# Sheet1_26Pin.net
KiCad netlist of a schematic drawn in Altium Designer
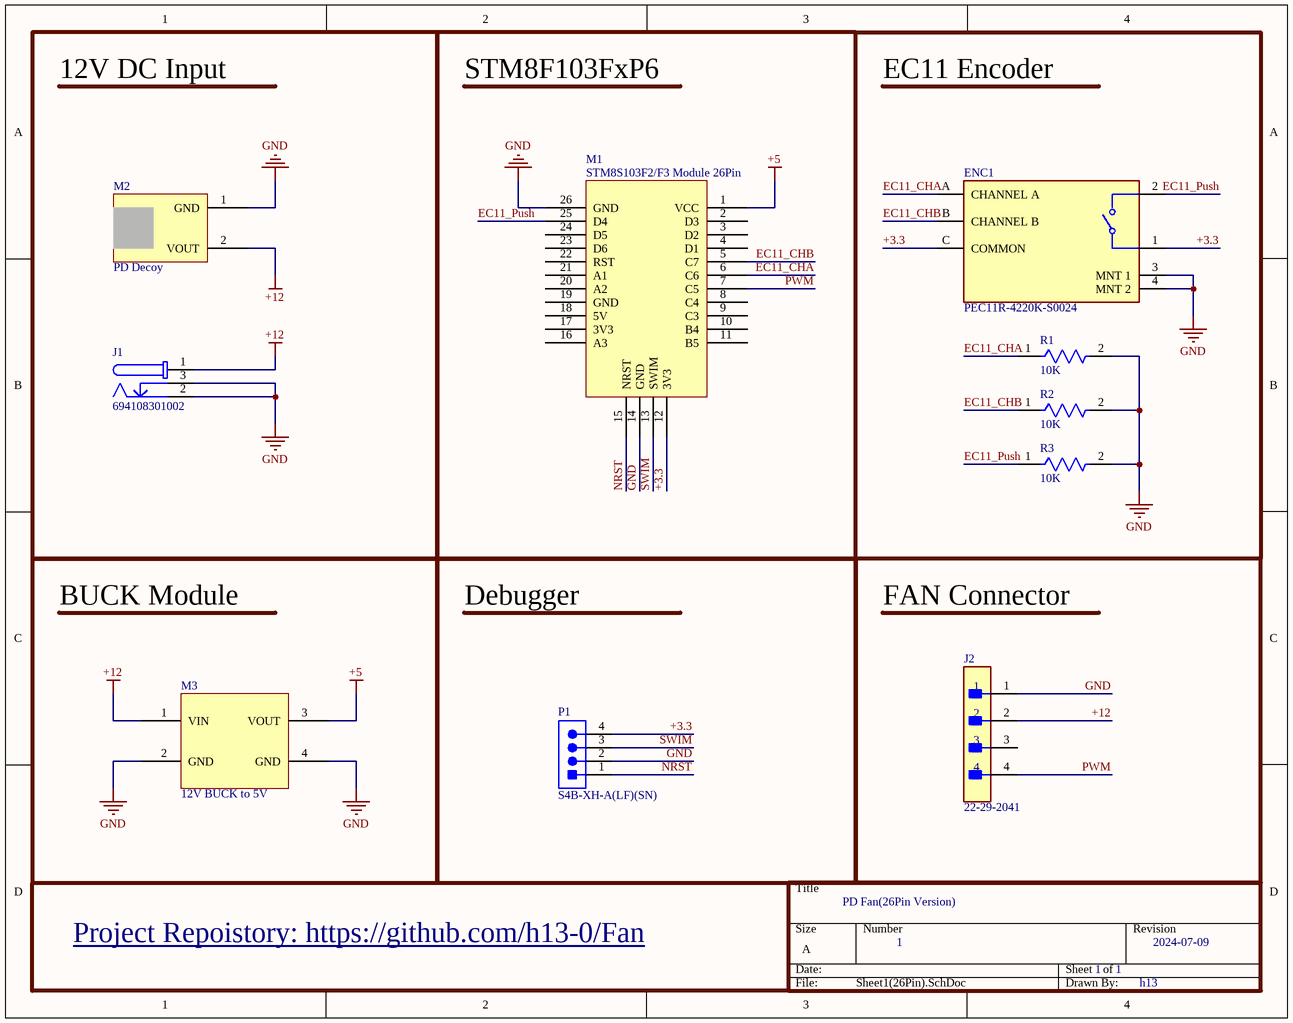
[diagram p0: Sheet1(26Pin).SchDoc]

(export (version "E")
  (design (tool "Eeschema 10.0.6"))
  (components
    (comp (ref "ENC1")
      (value "PEC11R-4220K-S0024")
      (footprint "EC11")
      (description "ROTARY ENCODER INCREMENTAL 24PPR")
      (libsource (lib "Altium Content Vault") (part "d75f9e24c474ed3fe2cf82f27e06f2a"))
    )
    (comp (ref "J1")
      (value "694108301002")
      (footprint "694108301002")
      (libsource (lib "Altium Content Vault") (part "DC Power Jack"))
    )
    (comp (ref "J2")
      (value "22-29-2041")
      (footprint "FP-22-29-2041-MFG")
      (description "CONN HEADER VERT 4POS 2.54MM")
      (libsource (lib "Altium Content Vault") (part "299a8cea1bdcbc3624fe62c390fa72c"))
    )
    (comp (ref "M1")
      (value "STM8S103F2/F3 Module 26Pin")
      (footprint "STM8FxP6 Module 26Pin")
      (libsource (lib "STM8S103F") (part "STM8S103F2/F3 Module"))
    )
    (comp (ref "M2") (value "PD Decoy") (footprint "PD Decoy") (libsource (lib "PD_Decoy") (part "PD Decoy")))
    (comp (ref "M3")
      (value "12V BUCK to 5V")
      (footprint "Buck Mini")
      (libsource (lib "BUCK_BOOST") (part "BUCK ¦ BOOST"))
    )
    (comp (ref "P1")
      (value "S4B-XH-A(LF)(SN)")
      (footprint "JST-S4B-XH-A(LF)(SN)_V")
      (libsource (lib "Altium Content Vault") (part "CN-1P-M-R4"))
    )
    (comp (ref "R1")
      (value "10K")
      (footprint "FP-MRS25-MFG")
      (description "RES 1K OHM 0.6W 1% AXIAL")
      (fields (field (name "TOLERANCE") "1%"))
      (libsource (lib "Altium Content Vault") (part "1029c3af85768c4190bb7ad29bc67b5"))
    )
    (comp (ref "R2")
      (value "10K")
      (footprint "FP-MRS25-MFG")
      (description "RES 1K OHM 0.6W 1% AXIAL")
      (fields (field (name "TOLERANCE") "1%"))
      (libsource (lib "Altium Content Vault") (part "1029c3af85768c4190bb7ad29bc67b5"))
    )
    (comp (ref "R3")
      (value "10K")
      (footprint "FP-MRS25-MFG")
      (description "RES 1K OHM 0.6W 1% AXIAL")
      (fields (field (name "TOLERANCE") "1%"))
      (libsource (lib "Altium Content Vault") (part "1029c3af85768c4190bb7ad29bc67b5"))
    )
  )
  (nets
    (net (code "1") (name "+5") (class "Default")
      (node (ref "M1") (pin "1") (pinfunction "VCC_1") (pintype "passive"))
      (node (ref "M3") (pin "3") (pinfunction "VOUT_3") (pintype "passive"))
    )
    (net (code "2") (name "+12") (class "Default")
      (node (ref "J1") (pin "1") (pinfunction "1_1") (pintype "passive"))
      (node (ref "J2") (pin "2") (pinfunction "2_2") (pintype "passive"))
      (node (ref "M2") (pin "2") (pinfunction "VOUT_2") (pintype "passive"))
      (node (ref "M3") (pin "1") (pinfunction "VIN_1") (pintype "passive"))
    )
    (net (code "3") (name "/+3.3") (class "Default")
      (node (ref "ENC1") (pin "1") (pinfunction "1_1") (pintype "passive"))
      (node (ref "ENC1") (pin "C") (pinfunction "COMMON_C") (pintype "passive"))
      (node (ref "M1") (pin "12") (pinfunction "3V3_12") (pintype "passive"))
      (node (ref "P1") (pin "4") (pinfunction "4_4") (pintype "passive"))
    )
    (net (code "4") (name "/EC11_CHA") (class "Default")
      (node (ref "ENC1") (pin "A") (pinfunction "CHANNEL_A_A") (pintype "passive"))
      (node (ref "M1") (pin "6") (pinfunction "C6_6") (pintype "passive"))
      (node (ref "R1") (pin "1") (pinfunction "1_1") (pintype "passive"))
    )
    (net (code "5") (name "/EC11_CHB") (class "Default")
      (node (ref "ENC1") (pin "B") (pinfunction "CHANNEL_B_B") (pintype "passive"))
      (node (ref "M1") (pin "5") (pinfunction "C7_5") (pintype "passive"))
      (node (ref "R2") (pin "1") (pinfunction "1_1") (pintype "passive"))
    )
    (net (code "6") (name "/EC11_Push") (class "Default")
      (node (ref "ENC1") (pin "2") (pinfunction "2_2") (pintype "passive"))
      (node (ref "M1") (pin "25") (pinfunction "D4_25") (pintype "passive"))
      (node (ref "R3") (pin "1") (pinfunction "1_1") (pintype "passive"))
    )
    (net (code "7") (name "/NRST") (class "Default")
      (node (ref "M1") (pin "15") (pinfunction "NRST_15") (pintype "passive"))
      (node (ref "P1") (pin "1") (pinfunction "1_1") (pintype "passive"))
    )
    (net (code "8") (name "/PWM") (class "Default")
      (node (ref "J2") (pin "4") (pinfunction "4_4") (pintype "passive"))
      (node (ref "M1") (pin "7") (pinfunction "C5_7") (pintype "passive"))
    )
    (net (code "9") (name "/SWIM") (class "Default")
      (node (ref "M1") (pin "13") (pinfunction "SWIM_13") (pintype "passive"))
      (node (ref "P1") (pin "3") (pinfunction "3_3") (pintype "passive"))
    )
    (net (code "10") (name "GND") (class "Default")
      (node (ref "ENC1") (pin "3") (pinfunction "MNT_1_3") (pintype "passive"))
      (node (ref "ENC1") (pin "4") (pinfunction "MNT_2_4") (pintype "passive"))
      (node (ref "J1") (pin "2") (pinfunction "2_2") (pintype "passive"))
      (node (ref "J1") (pin "3") (pinfunction "3_3") (pintype "passive"))
      (node (ref "J2") (pin "1") (pinfunction "1_1") (pintype "passive"))
      (node (ref "M1") (pin "14") (pinfunction "GND_14") (pintype "passive"))
      (node (ref "M1") (pin "26") (pinfunction "GND_26") (pintype "passive"))
      (node (ref "M2") (pin "1") (pinfunction "GND_1") (pintype "passive"))
      (node (ref "M3") (pin "2") (pinfunction "GND_2") (pintype "passive"))
      (node (ref "M3") (pin "4") (pinfunction "GND_4") (pintype "passive"))
      (node (ref "P1") (pin "2") (pinfunction "2_2") (pintype "passive"))
      (node (ref "R1") (pin "2") (pinfunction "2_2") (pintype "passive"))
      (node (ref "R2") (pin "2") (pinfunction "2_2") (pintype "passive"))
      (node (ref "R3") (pin "2") (pinfunction "2_2") (pintype "passive"))
    )
    (net (code "11") (name "unconnected-(J2-Pad3)") (class "Default")
      (node (ref "J2") (pin "3") (pinfunction "3_3") (pintype "passive"))
    )
    (net (code "12") (name "unconnected-(M1-3V3-Pad17)") (class "Default")
      (node (ref "M1") (pin "17") (pinfunction "3V3_17") (pintype "passive"))
    )
    (net (code "13") (name "unconnected-(M1-5V-Pad18)") (class "Default")
      (node (ref "M1") (pin "18") (pinfunction "5V_18") (pintype "passive"))
    )
    (net (code "14") (name "unconnected-(M1-A1-Pad21)") (class "Default")
      (node (ref "M1") (pin "21") (pinfunction "A1_21") (pintype "passive"))
    )
    (net (code "15") (name "unconnected-(M1-A2-Pad20)") (class "Default")
      (node (ref "M1") (pin "20") (pinfunction "A2_20") (pintype "passive"))
    )
    (net (code "16") (name "unconnected-(M1-A3-Pad16)") (class "Default")
      (node (ref "M1") (pin "16") (pinfunction "A3_16") (pintype "passive"))
    )
    (net (code "17") (name "unconnected-(M1-B4-Pad10)") (class "Default")
      (node (ref "M1") (pin "10") (pinfunction "B4_10") (pintype "passive"))
    )
    (net (code "18") (name "unconnected-(M1-B5-Pad11)") (class "Default")
      (node (ref "M1") (pin "11") (pinfunction "B5_11") (pintype "passive"))
    )
    (net (code "19") (name "unconnected-(M1-C3-Pad9)") (class "Default")
      (node (ref "M1") (pin "9") (pinfunction "C3_9") (pintype "passive"))
    )
    (net (code "20") (name "unconnected-(M1-C4-Pad8)") (class "Default")
      (node (ref "M1") (pin "8") (pinfunction "C4_8") (pintype "passive"))
    )
    (net (code "21") (name "unconnected-(M1-D1-Pad4)") (class "Default")
      (node (ref "M1") (pin "4") (pinfunction "D1_4") (pintype "passive"))
    )
    (net (code "22") (name "unconnected-(M1-D2-Pad3)") (class "Default")
      (node (ref "M1") (pin "3") (pinfunction "D2_3") (pintype "passive"))
    )
    (net (code "23") (name "unconnected-(M1-D3-Pad2)") (class "Default")
      (node (ref "M1") (pin "2") (pinfunction "D3_2") (pintype "passive"))
    )
    (net (code "24") (name "unconnected-(M1-D5-Pad24)") (class "Default")
      (node (ref "M1") (pin "24") (pinfunction "D5_24") (pintype "passive"))
    )
    (net (code "25") (name "unconnected-(M1-D6-Pad23)") (class "Default")
      (node (ref "M1") (pin "23") (pinfunction "D6_23") (pintype "passive"))
    )
    (net (code "26") (name "unconnected-(M1-GND-Pad19)") (class "Default")
      (node (ref "M1") (pin "19") (pinfunction "GND_19") (pintype "passive"))
    )
    (net (code "27") (name "unconnected-(M1-RST-Pad22)") (class "Default")
      (node (ref "M1") (pin "22") (pinfunction "RST_22") (pintype "passive"))
    )
  )
)
